# poas.net
KiCad netlist of a schematic drawn in EAGLE
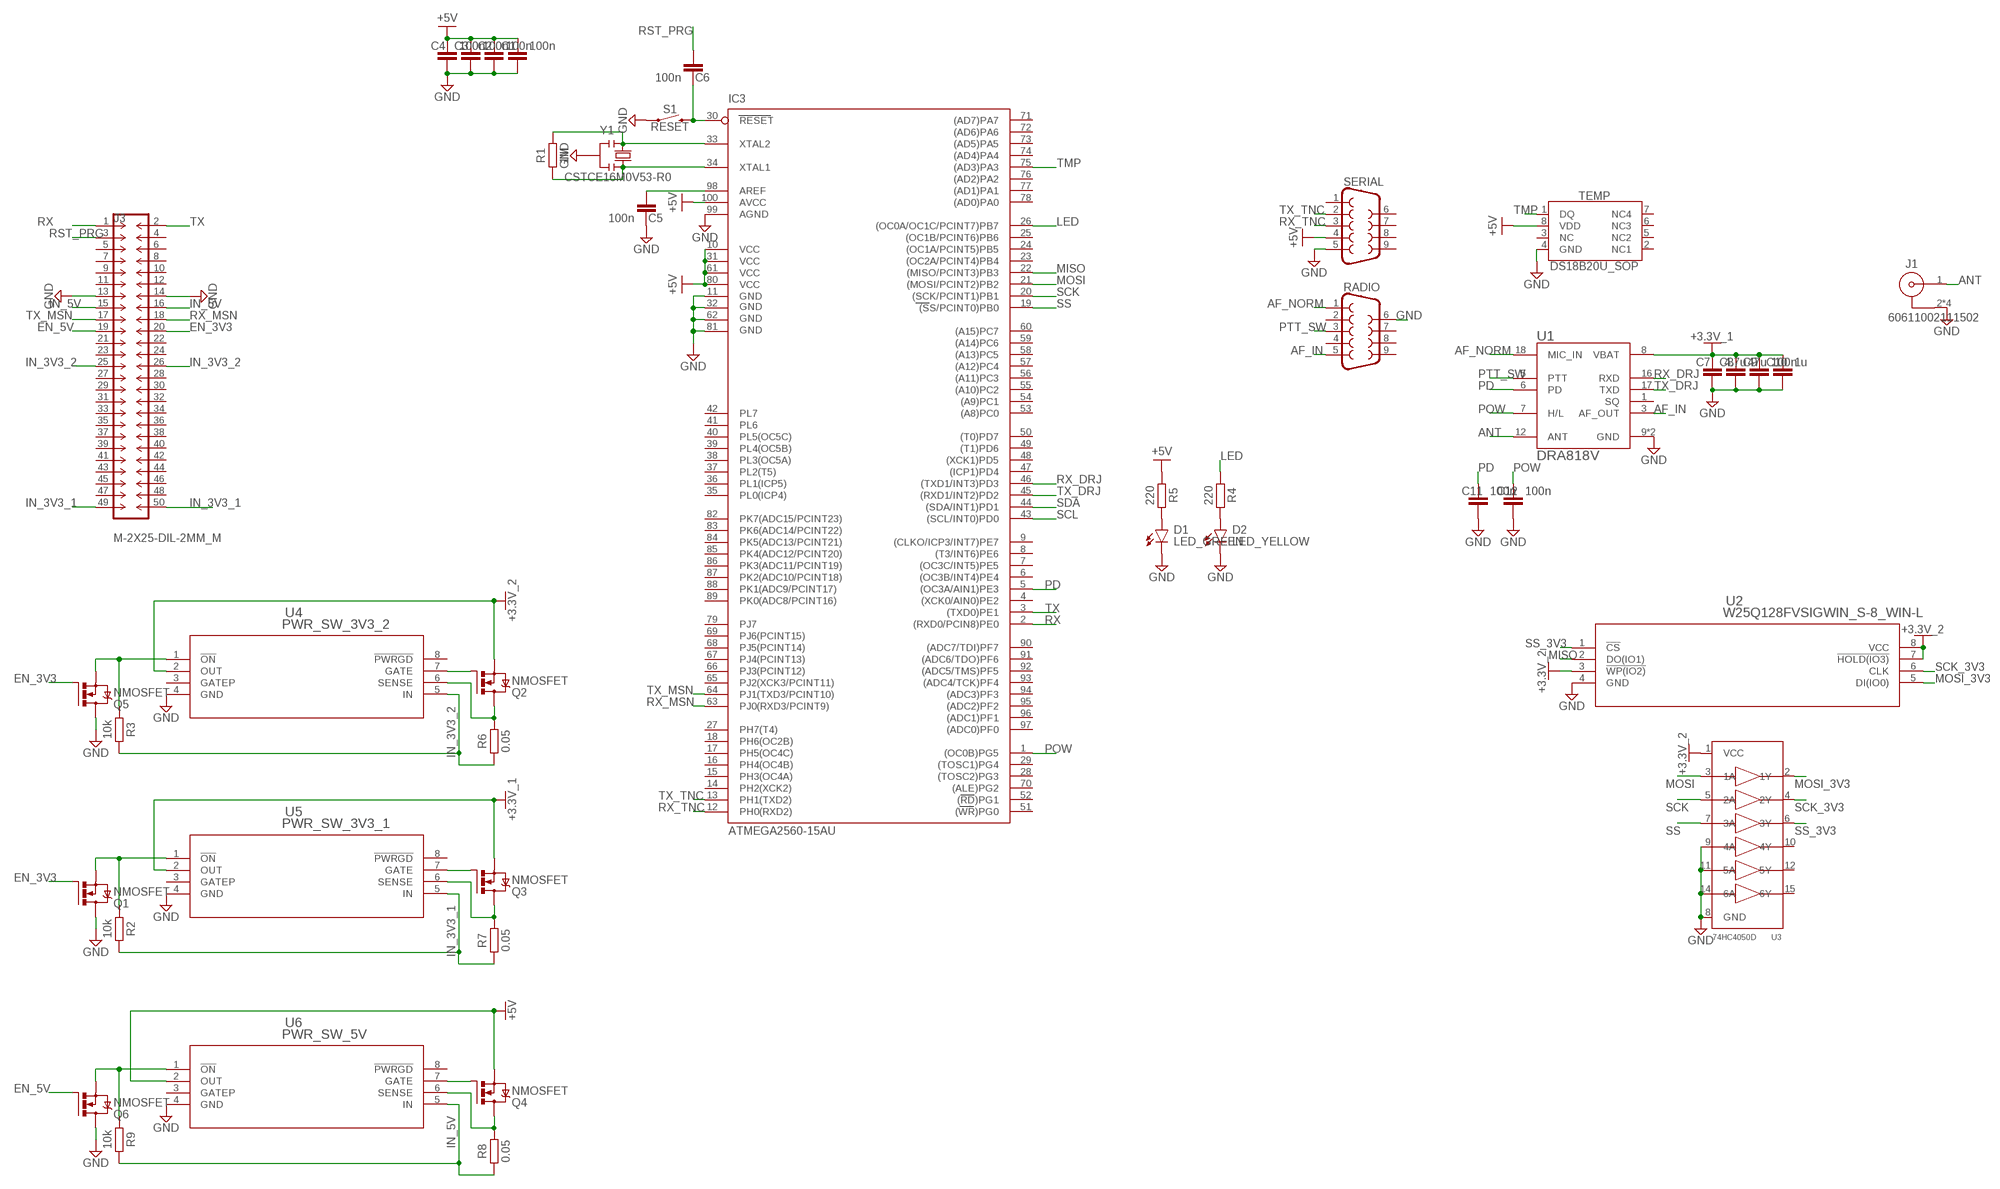
[diagram p0: schematic, sheet 1]

(export (version "E")
  (design (tool "Eeschema 10.0.6"))
  (components
    (comp (ref "C1")
      (value "100n")
      (footprint "eagle-import:CAPC1608X85")
      (libsource (lib "eagle-import") (part "CCHIP-0603(1608-METRIC)_"))
    )
    (comp (ref "C2")
      (value "100n")
      (footprint "eagle-import:CAPC1608X85")
      (libsource (lib "eagle-import") (part "CCHIP-0603(1608-METRIC)_"))
    )
    (comp (ref "C3")
      (value "100n")
      (footprint "eagle-import:CAPC1608X85")
      (libsource (lib "eagle-import") (part "CCHIP-0603(1608-METRIC)_"))
    )
    (comp (ref "C4")
      (value "100n")
      (footprint "eagle-import:CAPC1608X85")
      (libsource (lib "eagle-import") (part "CCHIP-0603(1608-METRIC)_"))
    )
    (comp (ref "C5")
      (value "100n")
      (footprint "eagle-import:CAPC1608X85")
      (libsource (lib "eagle-import") (part "CCHIP-0603(1608-METRIC)_"))
    )
    (comp (ref "C6")
      (value "100n")
      (footprint "eagle-import:CAPC1608X85")
      (libsource (lib "eagle-import") (part "CCHIP-0603(1608-METRIC)_"))
    )
    (comp (ref "C7")
      (value "4.7u")
      (footprint "eagle-import:CAPC1608X85")
      (libsource (lib "eagle-import") (part "CCHIP-0603(1608-METRIC)_"))
    )
    (comp (ref "C8")
      (value "47u")
      (footprint "eagle-import:CAPC1608X85")
      (libsource (lib "eagle-import") (part "CCHIP-0603(1608-METRIC)_"))
    )
    (comp (ref "C9")
      (value "100n")
      (footprint "eagle-import:CAPC1608X85")
      (libsource (lib "eagle-import") (part "CCHIP-0603(1608-METRIC)_"))
    )
    (comp (ref "C10")
      (value "1u")
      (footprint "eagle-import:CAPC1608X85")
      (libsource (lib "eagle-import") (part "CCHIP-0603(1608-METRIC)_"))
    )
    (comp (ref "C11")
      (value "100n")
      (footprint "eagle-import:CAPC1608X85")
      (libsource (lib "eagle-import") (part "CCHIP-0603(1608-METRIC)_"))
    )
    (comp (ref "C12")
      (value "100n")
      (footprint "eagle-import:CAPC1608X85")
      (libsource (lib "eagle-import") (part "CCHIP-0603(1608-METRIC)_"))
    )
    (comp (ref "D1")
      (value "LED_GREEN")
      (footprint "eagle-import:LEDC1608X55N_FLAT-G")
      (libsource (lib "eagle-import") (part "CHIP-FLAT-G_0603-0.55MM"))
    )
    (comp (ref "D2")
      (value "LED_YELLOW")
      (footprint "eagle-import:LEDC1608X55N_FLAT-Y")
      (libsource (lib "eagle-import") (part "CHIP-FLAT-Y_0603-0.55MM"))
    )
    (comp (ref "IC3")
      (value "ATMEGA2560-15AU")
      (footprint "eagle-import:TQFP100")
      (fields (field (name "PART_NUMBER") "ATMEGA2560-16AU"))
      (libsource (lib "eagle-import") (part "0023_ATMEGA2560-16AU"))
    )
    (comp (ref "J1")
      (value "60611002111502")
      (footprint "eagle-import:60611002111502")
      (libsource (lib "eagle-import") (part "60611002111502"))
    )
    (comp (ref "J3")
      (value "M-2X25-DIL-2MM_M")
      (footprint "eagle-import:DIL-2MM-2X25_M")
      (libsource (lib "eagle-import") (part "M-2X25-DIL-2MM_M"))
    )
    (comp (ref "Q1")
      (value "NMOSFET")
      (footprint "eagle-import:SOT23")
      (libsource (lib "eagle-import") (part "NMOSFETSOT23-GSD"))
    )
    (comp (ref "Q2")
      (value "NMOSFET")
      (footprint "eagle-import:SOT23")
      (libsource (lib "eagle-import") (part "NMOSFETSOT23-GSD"))
    )
    (comp (ref "Q3")
      (value "NMOSFET")
      (footprint "eagle-import:SOT23")
      (libsource (lib "eagle-import") (part "NMOSFETSOT23-GSD"))
    )
    (comp (ref "Q4")
      (value "NMOSFET")
      (footprint "eagle-import:SOT23")
      (libsource (lib "eagle-import") (part "NMOSFETSOT23-GSD"))
    )
    (comp (ref "Q5")
      (value "NMOSFET")
      (footprint "eagle-import:SOT23")
      (libsource (lib "eagle-import") (part "NMOSFETSOT23-GSD"))
    )
    (comp (ref "Q6")
      (value "NMOSFET")
      (footprint "eagle-import:SOT23")
      (libsource (lib "eagle-import") (part "NMOSFETSOT23-GSD"))
    )
    (comp (ref "R1")
      (value "1M")
      (footprint "eagle-import:RESC1608X60")
      (libsource (lib "eagle-import") (part "RCHIP-0603(1608-METRIC)_"))
    )
    (comp (ref "R2")
      (value "10k")
      (footprint "eagle-import:RESC1608X60")
      (libsource (lib "eagle-import") (part "RCHIP-0603(1608-METRIC)_"))
    )
    (comp (ref "R3")
      (value "10k")
      (footprint "eagle-import:RESC1608X60")
      (libsource (lib "eagle-import") (part "RCHIP-0603(1608-METRIC)_"))
    )
    (comp (ref "R4")
      (value "220")
      (footprint "eagle-import:RESC1608X60")
      (libsource (lib "eagle-import") (part "RCHIP-0603(1608-METRIC)_"))
    )
    (comp (ref "R5")
      (value "220")
      (footprint "eagle-import:RESC1608X60")
      (libsource (lib "eagle-import") (part "RCHIP-0603(1608-METRIC)_"))
    )
    (comp (ref "R6")
      (value "0.05")
      (footprint "eagle-import:RESC1608X60")
      (libsource (lib "eagle-import") (part "RCHIP-0603(1608-METRIC)_"))
    )
    (comp (ref "R7")
      (value "0.05")
      (footprint "eagle-import:RESC1608X60")
      (libsource (lib "eagle-import") (part "RCHIP-0603(1608-METRIC)_"))
    )
    (comp (ref "R8")
      (value "0.05")
      (footprint "eagle-import:RESC1608X60")
      (libsource (lib "eagle-import") (part "RCHIP-0603(1608-METRIC)_"))
    )
    (comp (ref "R9")
      (value "10k")
      (footprint "eagle-import:RESC1608X60")
      (libsource (lib "eagle-import") (part "RCHIP-0603(1608-METRIC)_"))
    )
    (comp (ref "RADIO")
      (value "DB9MALE")
      (footprint "eagle-import:DB9_MALE")
      (libsource (lib "eagle-import") (part "DB9MALE"))
    )
    (comp (ref "S1")
      (value "RESET")
      (footprint "eagle-import:TACTILE_SWITCH_SMD_6.2MM_TALL")
      (libsource (lib "eagle-import") (part "MOMENTARY-SWITCH-SPST-SMD-6.2MM-TALL"))
    )
    (comp (ref "SERIAL")
      (value "DB9MALE")
      (footprint "eagle-import:DB9_MALE")
      (libsource (lib "eagle-import") (part "DB9MALE"))
    )
    (comp (ref "TEMP")
      (value "DS18B20U_SOP")
      (footprint "eagle-import:SOP65P491X110-8N")
      (libsource (lib "eagle-import") (part "DS18B20U_SOP"))
    )
    (comp (ref "U1")
      (value "DRA818V")
      (footprint "eagle-import:DORJI_DRA818V")
      (fields (field (name "MANUFACTURER") "DORJI"))
      (libsource (lib "eagle-import") (part "DRA818V"))
    )
    (comp (ref "U2")
      (value "W25Q128FVSIGWIN_S-8_WIN-L")
      (footprint "eagle-import:WIN_S-8_WIN-L")
      (fields
        (field (name "MANUFACTURER_PART_NUMBER") "W25Q128FVSIG")
        (field (name "COPYRIGHT") "Copyright (C) 2023 Ultra Librarian. All rights reserved.")
      )
      (libsource (lib "eagle-import") (part "W25Q128FVSIGWIN_S-8_WIN-L"))
    )
    (comp (ref "U3")
      (value "74HC4050D")
      (footprint "eagle-import:TSSOP16")
      (libsource (lib "eagle-import") (part "74HC4050DTSSOP"))
    )
    (comp (ref "U4")
      (value "PWR_SW_3V3_2")
      (footprint "eagle-import:TSOT-23_TS8_LIT-L")
      (fields
        (field (name "MANUFACTURER_PART_NUMBER") "LTC4361CTS8-2#TRMPBF")
        (field (name "COPYRIGHT") "Copyright (C) 2023 Ultra Librarian. All rights reserved.")
      )
      (libsource (lib "eagle-import") (part "LTC4361CTS8-2TRMPBFTSOT-23_TS8_LIT-L"))
    )
    (comp (ref "U5")
      (value "PWR_SW_3V3_1")
      (footprint "eagle-import:TSOT-23_TS8_LIT-L")
      (fields
        (field (name "MANUFACTURER_PART_NUMBER") "LTC4361CTS8-2#TRMPBF")
        (field (name "COPYRIGHT") "Copyright (C) 2023 Ultra Librarian. All rights reserved.")
      )
      (libsource (lib "eagle-import") (part "LTC4361CTS8-2TRMPBFTSOT-23_TS8_LIT-L"))
    )
    (comp (ref "U6")
      (value "PWR_SW_5V")
      (footprint "eagle-import:TSOT-23_TS8_LIT-L")
      (fields
        (field (name "MANUFACTURER_PART_NUMBER") "LTC4361CTS8-2#TRMPBF")
        (field (name "COPYRIGHT") "Copyright (C) 2023 Ultra Librarian. All rights reserved.")
      )
      (libsource (lib "eagle-import") (part "LTC4361CTS8-2TRMPBFTSOT-23_TS8_LIT-L"))
    )
    (comp (ref "Y1")
      (value "CSTCE16M0V53-R0")
      (footprint "eagle-import:RESONATOR")
      (libsource (lib "eagle-import") (part "0011_CSTCE16M0V53-R0"))
    )
  )
  (nets
    (net (code "1") (name "+3.3V_1") (class "Default")
      (node (ref "C10") (pin "1") (pinfunction "1_1") (pintype "passive"))
      (node (ref "C7") (pin "1") (pinfunction "1_1") (pintype "passive"))
      (node (ref "C8") (pin "1") (pinfunction "1_1") (pintype "passive"))
      (node (ref "C9") (pin "1") (pinfunction "1_1") (pintype "passive"))
      (node (ref "Q3") (pin "2") (pinfunction "S_2") (pintype "passive"))
      (node (ref "U1") (pin "8") (pinfunction "VBAT_8") (pintype "power_in"))
      (node (ref "U5") (pin "2") (pinfunction "OUT_2") (pintype "output"))
    )
    (net (code "2") (name "+3.3V_2") (class "Default")
      (node (ref "Q2") (pin "2") (pinfunction "S_2") (pintype "passive"))
      (node (ref "U2") (pin "3") (pinfunction "~{WP(IO2})_3") (pintype "bidirectional"))
      (node (ref "U2") (pin "7") (pinfunction "~{HOLD(IO3})_7") (pintype "bidirectional"))
      (node (ref "U2") (pin "8") (pinfunction "VCC_8") (pintype "power_in"))
      (node (ref "U3") (pin "1") (pinfunction "VCC_1") (pintype "bidirectional"))
      (node (ref "U4") (pin "2") (pinfunction "OUT_2") (pintype "output"))
    )
    (net (code "3") (name "+5V") (class "Default")
      (node (ref "C1") (pin "1") (pinfunction "1_1") (pintype "passive"))
      (node (ref "C2") (pin "1") (pinfunction "1_1") (pintype "passive"))
      (node (ref "C3") (pin "1") (pinfunction "1_1") (pintype "passive"))
      (node (ref "C4") (pin "1") (pinfunction "1_1") (pintype "passive"))
      (node (ref "IC3") (pin "10") (pinfunction "VCC_10") (pintype "power_in"))
      (node (ref "IC3") (pin "100") (pinfunction "AVCC_100") (pintype "power_in"))
      (node (ref "IC3") (pin "31") (pinfunction "VCC1_31") (pintype "power_in"))
      (node (ref "IC3") (pin "61") (pinfunction "VCC2_61") (pintype "power_in"))
      (node (ref "IC3") (pin "80") (pinfunction "VCC3_80") (pintype "power_in"))
      (node (ref "Q4") (pin "2") (pinfunction "S_2") (pintype "passive"))
      (node (ref "R5") (pin "1") (pinfunction "1_1") (pintype "passive"))
      (node (ref "SERIAL") (pin "4") (pinfunction "4_4") (pintype "passive"))
      (node (ref "TEMP") (pin "8") (pinfunction "VDD_8") (pintype "bidirectional"))
      (node (ref "U6") (pin "2") (pinfunction "OUT_2") (pintype "output"))
    )
    (net (code "4") (name "/AF_IN") (class "Default")
      (node (ref "RADIO") (pin "5") (pinfunction "5_5") (pintype "passive"))
      (node (ref "U1") (pin "3") (pinfunction "AF_OUT_3") (pintype "output"))
    )
    (net (code "5") (name "/AF_NORM") (class "Default")
      (node (ref "RADIO") (pin "1") (pinfunction "1_1") (pintype "passive"))
      (node (ref "U1") (pin "18") (pinfunction "MIC_IN_18") (pintype "input"))
    )
    (net (code "6") (name "/ANT") (class "Default")
      (node (ref "J1") (pin "1") (pinfunction "1_1") (pintype "passive"))
      (node (ref "U1") (pin "12") (pinfunction "ANT_12") (pintype "passive"))
    )
    (net (code "7") (name "/EN_3V3") (class "Default")
      (node (ref "J3") (pin "20") (pinfunction "20_20") (pintype "passive"))
      (node (ref "Q1") (pin "1") (pinfunction "G_1") (pintype "passive"))
      (node (ref "Q5") (pin "1") (pinfunction "G_1") (pintype "passive"))
    )
    (net (code "8") (name "/EN_5V") (class "Default")
      (node (ref "J3") (pin "19") (pinfunction "19_19") (pintype "passive"))
      (node (ref "Q6") (pin "1") (pinfunction "G_1") (pintype "passive"))
    )
    (net (code "9") (name "/IN_3V3_1") (class "Default")
      (node (ref "J3") (pin "49") (pinfunction "49_49") (pintype "passive"))
      (node (ref "J3") (pin "50") (pinfunction "50_50") (pintype "passive"))
      (node (ref "R2") (pin "2") (pinfunction "2_2") (pintype "passive"))
      (node (ref "R7") (pin "1") (pinfunction "1_1") (pintype "passive"))
      (node (ref "U5") (pin "5") (pinfunction "IN_5") (pintype "input"))
    )
    (net (code "10") (name "/IN_3V3_2") (class "Default")
      (node (ref "J3") (pin "25") (pinfunction "25_25") (pintype "passive"))
      (node (ref "J3") (pin "26") (pinfunction "26_26") (pintype "passive"))
      (node (ref "R3") (pin "2") (pinfunction "2_2") (pintype "passive"))
      (node (ref "R6") (pin "1") (pinfunction "1_1") (pintype "passive"))
      (node (ref "U4") (pin "5") (pinfunction "IN_5") (pintype "input"))
    )
    (net (code "11") (name "/IN_5V") (class "Default")
      (node (ref "J3") (pin "15") (pinfunction "15_15") (pintype "passive"))
      (node (ref "J3") (pin "16") (pinfunction "16_16") (pintype "passive"))
      (node (ref "R8") (pin "1") (pinfunction "1_1") (pintype "passive"))
      (node (ref "R9") (pin "2") (pinfunction "2_2") (pintype "passive"))
      (node (ref "U6") (pin "5") (pinfunction "IN_5") (pintype "input"))
    )
    (net (code "12") (name "/LED") (class "Default")
      (node (ref "IC3") (pin "26") (pinfunction "(OC0A/OC1C/PCINT7)PB7_26") (pintype "bidirectional"))
      (node (ref "R4") (pin "1") (pinfunction "1_1") (pintype "passive"))
    )
    (net (code "13") (name "/MISO") (class "Default")
      (node (ref "IC3") (pin "22") (pinfunction "(MISO/PCINT3)PB3_22") (pintype "bidirectional"))
      (node (ref "U2") (pin "2") (pinfunction "DO(IO1)_2") (pintype "bidirectional"))
    )
    (net (code "14") (name "/MOSI") (class "Default")
      (node (ref "IC3") (pin "21") (pinfunction "(MOSI/PCINT2)PB2_21") (pintype "bidirectional"))
      (node (ref "U3") (pin "3") (pinfunction "1A_3") (pintype "bidirectional"))
    )
    (net (code "15") (name "/MOSI_3V3") (class "Default")
      (node (ref "U2") (pin "5") (pinfunction "DI(IO0)_5") (pintype "bidirectional"))
      (node (ref "U3") (pin "2") (pinfunction "1Y_2") (pintype "bidirectional"))
    )
    (net (code "16") (name "/PD") (class "Default")
      (node (ref "C11") (pin "1") (pinfunction "1_1") (pintype "passive"))
      (node (ref "IC3") (pin "5") (pinfunction "(OC3A/AIN1)PE3_5") (pintype "bidirectional"))
      (node (ref "U1") (pin "6") (pinfunction "PD_6") (pintype "input"))
    )
    (net (code "17") (name "/POW") (class "Default")
      (node (ref "C12") (pin "1") (pinfunction "1_1") (pintype "passive"))
      (node (ref "IC3") (pin "1") (pinfunction "(OC0B)PG5_1") (pintype "bidirectional"))
      (node (ref "U1") (pin "7") (pinfunction "H/L_7") (pintype "input"))
    )
    (net (code "18") (name "/PTT_SW") (class "Default")
      (node (ref "RADIO") (pin "3") (pinfunction "3_3") (pintype "passive"))
      (node (ref "U1") (pin "5") (pinfunction "PTT_5") (pintype "input"))
    )
    (net (code "19") (name "/RST_PRG") (class "Default")
      (node (ref "C6") (pin "2") (pinfunction "2_2") (pintype "passive"))
      (node (ref "J3") (pin "3") (pinfunction "3_3") (pintype "passive"))
    )
    (net (code "20") (name "/RX") (class "Default")
      (node (ref "IC3") (pin "2") (pinfunction "(RXD0/PCIN8)PE0_2") (pintype "bidirectional"))
      (node (ref "J3") (pin "1") (pinfunction "1_1") (pintype "passive"))
    )
    (net (code "21") (name "/RX_DRJ") (class "Default")
      (node (ref "IC3") (pin "46") (pinfunction "(TXD1/INT3)PD3_46") (pintype "bidirectional"))
      (node (ref "U1") (pin "16") (pinfunction "RXD_16") (pintype "input"))
    )
    (net (code "22") (name "/RX_MSN") (class "Default")
      (node (ref "IC3") (pin "63") (pinfunction "PJ0(RXD3/PCINT9)_63") (pintype "bidirectional"))
      (node (ref "J3") (pin "18") (pinfunction "18_18") (pintype "passive"))
    )
    (net (code "23") (name "/RX_TNC") (class "Default")
      (node (ref "IC3") (pin "12") (pinfunction "PH0(RXD2)_12") (pintype "bidirectional"))
      (node (ref "SERIAL") (pin "3") (pinfunction "3_3") (pintype "passive"))
    )
    (net (code "24") (name "/SCK") (class "Default")
      (node (ref "IC3") (pin "20") (pinfunction "(SCK/PCINT1)PB1_20") (pintype "bidirectional"))
      (node (ref "U3") (pin "5") (pinfunction "2A_5") (pintype "bidirectional"))
    )
    (net (code "25") (name "/SCK_3V3") (class "Default")
      (node (ref "U2") (pin "6") (pinfunction "CLK_6") (pintype "input"))
      (node (ref "U3") (pin "4") (pinfunction "2Y_4") (pintype "bidirectional"))
    )
    (net (code "26") (name "/SCL") (class "Default")
      (node (ref "IC3") (pin "43") (pinfunction "(SCL/INT0)PD0_43") (pintype "bidirectional"))
    )
    (net (code "27") (name "/SDA") (class "Default")
      (node (ref "IC3") (pin "44") (pinfunction "(SDA/INT1)PD1_44") (pintype "bidirectional"))
    )
    (net (code "28") (name "/SS") (class "Default")
      (node (ref "IC3") (pin "19") (pinfunction "(SS/PCINT0)PB0_19") (pintype "bidirectional"))
      (node (ref "U3") (pin "7") (pinfunction "3A_7") (pintype "bidirectional"))
    )
    (net (code "29") (name "/SS_3V3") (class "Default")
      (node (ref "U2") (pin "1") (pinfunction "~{CS}_1") (pintype "input"))
      (node (ref "U3") (pin "6") (pinfunction "3Y_6") (pintype "bidirectional"))
    )
    (net (code "30") (name "/TMP") (class "Default")
      (node (ref "IC3") (pin "75") (pinfunction "(AD3)PA3_75") (pintype "bidirectional"))
      (node (ref "TEMP") (pin "1") (pinfunction "DQ_1") (pintype "bidirectional"))
    )
    (net (code "31") (name "/TX") (class "Default")
      (node (ref "IC3") (pin "3") (pinfunction "(TXD0)PE1_3") (pintype "bidirectional"))
      (node (ref "J3") (pin "2") (pinfunction "2_2") (pintype "passive"))
    )
    (net (code "32") (name "/TX_DRJ") (class "Default")
      (node (ref "IC3") (pin "45") (pinfunction "(RXD1/INT2)PD2_45") (pintype "bidirectional"))
      (node (ref "U1") (pin "17") (pinfunction "TXD_17") (pintype "output"))
    )
    (net (code "33") (name "/TX_MSN") (class "Default")
      (node (ref "IC3") (pin "64") (pinfunction "PJ1(TXD3/PCINT10)_64") (pintype "bidirectional"))
      (node (ref "J3") (pin "17") (pinfunction "17_17") (pintype "passive"))
    )
    (net (code "34") (name "/TX_TNC") (class "Default")
      (node (ref "IC3") (pin "13") (pinfunction "PH1(TXD2)_13") (pintype "bidirectional"))
      (node (ref "SERIAL") (pin "2") (pinfunction "2_2") (pintype "passive"))
    )
    (net (code "35") (name "GND") (class "Default")
      (node (ref "C1") (pin "2") (pinfunction "2_2") (pintype "passive"))
      (node (ref "C10") (pin "2") (pinfunction "2_2") (pintype "passive"))
      (node (ref "C11") (pin "2") (pinfunction "2_2") (pintype "passive"))
      (node (ref "C12") (pin "2") (pinfunction "2_2") (pintype "passive"))
      (node (ref "C2") (pin "2") (pinfunction "2_2") (pintype "passive"))
      (node (ref "C3") (pin "2") (pinfunction "2_2") (pintype "passive"))
      (node (ref "C4") (pin "2") (pinfunction "2_2") (pintype "passive"))
      (node (ref "C5") (pin "1") (pinfunction "1_1") (pintype "passive"))
      (node (ref "C7") (pin "2") (pinfunction "2_2") (pintype "passive"))
      (node (ref "C8") (pin "2") (pinfunction "2_2") (pintype "passive"))
      (node (ref "C9") (pin "2") (pinfunction "2_2") (pintype "passive"))
      (node (ref "D1") (pin "C") (pinfunction "C_C") (pintype "passive"))
      (node (ref "D2") (pin "C") (pinfunction "C_C") (pintype "passive"))
      (node (ref "IC3") (pin "11") (pinfunction "GND_11") (pintype "power_in"))
      (node (ref "IC3") (pin "32") (pinfunction "GND1_32") (pintype "power_in"))
      (node (ref "IC3") (pin "62") (pinfunction "GND2_62") (pintype "power_in"))
      (node (ref "IC3") (pin "81") (pinfunction "GND3_81") (pintype "power_in"))
      (node (ref "IC3") (pin "99") (pinfunction "AGND_99") (pintype "power_in"))
      (node (ref "J1") (pin "2") (pinfunction "2_2") (pintype "passive"))
      (node (ref "J1") (pin "3") (pinfunction "2_3") (pintype "passive"))
      (node (ref "J1") (pin "4") (pinfunction "2_4") (pintype "passive"))
      (node (ref "J1") (pin "5") (pinfunction "2_5") (pintype "passive"))
      (node (ref "J3") (pin "13") (pinfunction "13_13") (pintype "passive"))
      (node (ref "J3") (pin "14") (pinfunction "14_14") (pintype "passive"))
      (node (ref "Q1") (pin "3") (pinfunction "D_3") (pintype "passive"))
      (node (ref "Q5") (pin "3") (pinfunction "D_3") (pintype "passive"))
      (node (ref "Q6") (pin "3") (pinfunction "D_3") (pintype "passive"))
      (node (ref "RADIO") (pin "6") (pinfunction "6_6") (pintype "passive"))
      (node (ref "S1") (pin "A2") (pinfunction "1_A2") (pintype "passive"))
      (node (ref "SERIAL") (pin "5") (pinfunction "5_5") (pintype "passive"))
      (node (ref "TEMP") (pin "4") (pinfunction "GND_4") (pintype "bidirectional"))
      (node (ref "U1") (pin "10") (pinfunction "GND_10") (pintype "power_in"))
      (node (ref "U1") (pin "9") (pinfunction "GND_9") (pintype "power_in"))
      (node (ref "U2") (pin "4") (pinfunction "GND_4") (pintype "power_in"))
      (node (ref "U3") (pin "11") (pinfunction "5A_11") (pintype "bidirectional"))
      (node (ref "U3") (pin "14") (pinfunction "6A_14") (pintype "bidirectional"))
      (node (ref "U3") (pin "8") (pinfunction "GND_8") (pintype "bidirectional"))
      (node (ref "U3") (pin "9") (pinfunction "4A_9") (pintype "bidirectional"))
      (node (ref "U4") (pin "4") (pinfunction "GND_4") (pintype "power_in"))
      (node (ref "U5") (pin "4") (pinfunction "GND_4") (pintype "power_in"))
      (node (ref "U6") (pin "4") (pinfunction "GND_4") (pintype "power_in"))
      (node (ref "Y1") (pin "2") (pinfunction "2_2") (pintype "passive"))
    )
    (net (code "36") (name "Net-(D1-PadA)") (class "Default")
      (node (ref "D1") (pin "A") (pinfunction "A_A") (pintype "passive"))
      (node (ref "R5") (pin "2") (pinfunction "2_2") (pintype "passive"))
    )
    (net (code "37") (name "Net-(D2-PadA)") (class "Default")
      (node (ref "D2") (pin "A") (pinfunction "A_A") (pintype "passive"))
      (node (ref "R4") (pin "2") (pinfunction "2_2") (pintype "passive"))
    )
    (net (code "38") (name "Net-(IC3-AREF)") (class "Default")
      (node (ref "C5") (pin "2") (pinfunction "2_2") (pintype "passive"))
      (node (ref "IC3") (pin "98") (pinfunction "AREF_98") (pintype "bidirectional"))
    )
    (net (code "39") (name "Net-(IC3-RESET)") (class "Default")
      (node (ref "C6") (pin "1") (pinfunction "1_1") (pintype "passive"))
      (node (ref "IC3") (pin "30") (pinfunction "RESET_30") (pintype "input"))
      (node (ref "S1") (pin "B2") (pinfunction "2_B2") (pintype "passive"))
    )
    (net (code "40") (name "Net-(IC3-XTAL1)") (class "Default")
      (node (ref "IC3") (pin "34") (pinfunction "XTAL1_34") (pintype "input"))
      (node (ref "R1") (pin "1") (pinfunction "1_1") (pintype "passive"))
      (node (ref "Y1") (pin "3") (pinfunction "3_3") (pintype "passive"))
    )
    (net (code "41") (name "Net-(IC3-XTAL2)") (class "Default")
      (node (ref "IC3") (pin "33") (pinfunction "XTAL2_33") (pintype "output"))
      (node (ref "R1") (pin "2") (pinfunction "2_2") (pintype "passive"))
      (node (ref "Y1") (pin "1") (pinfunction "1_1") (pintype "passive"))
    )
    (net (code "42") (name "Net-(Q1-S)") (class "Default")
      (node (ref "Q1") (pin "2") (pinfunction "S_2") (pintype "passive"))
      (node (ref "R2") (pin "1") (pinfunction "1_1") (pintype "passive"))
      (node (ref "U5") (pin "1") (pinfunction "~{ON}_1") (pintype "input"))
    )
    (net (code "43") (name "Net-(Q2-D)") (class "Default")
      (node (ref "Q2") (pin "3") (pinfunction "D_3") (pintype "passive"))
      (node (ref "R6") (pin "2") (pinfunction "2_2") (pintype "passive"))
      (node (ref "U4") (pin "6") (pinfunction "SENSE_6") (pintype "input"))
    )
    (net (code "44") (name "Net-(Q2-G)") (class "Default")
      (node (ref "Q2") (pin "1") (pinfunction "G_1") (pintype "passive"))
      (node (ref "U4") (pin "7") (pinfunction "GATE_7") (pintype "passive"))
    )
    (net (code "45") (name "Net-(Q3-D)") (class "Default")
      (node (ref "Q3") (pin "3") (pinfunction "D_3") (pintype "passive"))
      (node (ref "R7") (pin "2") (pinfunction "2_2") (pintype "passive"))
      (node (ref "U5") (pin "6") (pinfunction "SENSE_6") (pintype "input"))
    )
    (net (code "46") (name "Net-(Q3-G)") (class "Default")
      (node (ref "Q3") (pin "1") (pinfunction "G_1") (pintype "passive"))
      (node (ref "U5") (pin "7") (pinfunction "GATE_7") (pintype "passive"))
    )
    (net (code "47") (name "Net-(Q4-D)") (class "Default")
      (node (ref "Q4") (pin "3") (pinfunction "D_3") (pintype "passive"))
      (node (ref "R8") (pin "2") (pinfunction "2_2") (pintype "passive"))
      (node (ref "U6") (pin "6") (pinfunction "SENSE_6") (pintype "input"))
    )
    (net (code "48") (name "Net-(Q4-G)") (class "Default")
      (node (ref "Q4") (pin "1") (pinfunction "G_1") (pintype "passive"))
      (node (ref "U6") (pin "7") (pinfunction "GATE_7") (pintype "passive"))
    )
    (net (code "49") (name "Net-(Q5-S)") (class "Default")
      (node (ref "Q5") (pin "2") (pinfunction "S_2") (pintype "passive"))
      (node (ref "R3") (pin "1") (pinfunction "1_1") (pintype "passive"))
      (node (ref "U4") (pin "1") (pinfunction "~{ON}_1") (pintype "input"))
    )
    (net (code "50") (name "Net-(Q6-S)") (class "Default")
      (node (ref "Q6") (pin "2") (pinfunction "S_2") (pintype "passive"))
      (node (ref "R9") (pin "1") (pinfunction "1_1") (pintype "passive"))
      (node (ref "U6") (pin "1") (pinfunction "~{ON}_1") (pintype "input"))
    )
    (net (code "51") (name "unconnected-(IC3-(A8)PC0-Pad53)") (class "Default")
      (node (ref "IC3") (pin "53") (pinfunction "(A8)PC0_53") (pintype "bidirectional"))
    )
    (net (code "52") (name "unconnected-(IC3-(A9)PC1-Pad54)") (class "Default")
      (node (ref "IC3") (pin "54") (pinfunction "(A9)PC1_54") (pintype "bidirectional"))
    )
    (net (code "53") (name "unconnected-(IC3-(A10)PC2-Pad55)") (class "Default")
      (node (ref "IC3") (pin "55") (pinfunction "(A10)PC2_55") (pintype "bidirectional"))
    )
    (net (code "54") (name "unconnected-(IC3-(A11)PC3-Pad56)") (class "Default")
      (node (ref "IC3") (pin "56") (pinfunction "(A11)PC3_56") (pintype "bidirectional"))
    )
    (net (code "55") (name "unconnected-(IC3-(A12)PC4-Pad57)") (class "Default")
      (node (ref "IC3") (pin "57") (pinfunction "(A12)PC4_57") (pintype "bidirectional"))
    )
    (net (code "56") (name "unconnected-(IC3-(A13)PC5-Pad58)") (class "Default")
      (node (ref "IC3") (pin "58") (pinfunction "(A13)PC5_58") (pintype "bidirectional"))
    )
    (net (code "57") (name "unconnected-(IC3-(A14)PC6-Pad59)") (class "Default")
      (node (ref "IC3") (pin "59") (pinfunction "(A14)PC6_59") (pintype "bidirectional"))
    )
    (net (code "58") (name "unconnected-(IC3-(A15)PC7-Pad60)") (class "Default")
      (node (ref "IC3") (pin "60") (pinfunction "(A15)PC7_60") (pintype "bidirectional"))
    )
    (net (code "59") (name "unconnected-(IC3-(AD0)PA0-Pad78)") (class "Default")
      (node (ref "IC3") (pin "78") (pinfunction "(AD0)PA0_78") (pintype "bidirectional"))
    )
    (net (code "60") (name "unconnected-(IC3-(AD1)PA1-Pad77)") (class "Default")
      (node (ref "IC3") (pin "77") (pinfunction "(AD1)PA1_77") (pintype "bidirectional"))
    )
    (net (code "61") (name "unconnected-(IC3-(AD2)PA2-Pad76)") (class "Default")
      (node (ref "IC3") (pin "76") (pinfunction "(AD2)PA2_76") (pintype "bidirectional"))
    )
    (net (code "62") (name "unconnected-(IC3-(AD4)PA4-Pad74)") (class "Default")
      (node (ref "IC3") (pin "74") (pinfunction "(AD4)PA4_74") (pintype "bidirectional"))
    )
    (net (code "63") (name "unconnected-(IC3-(AD5)PA5-Pad73)") (class "Default")
      (node (ref "IC3") (pin "73") (pinfunction "(AD5)PA5_73") (pintype "bidirectional"))
    )
    (net (code "64") (name "unconnected-(IC3-(AD6)PA6-Pad72)") (class "Default")
      (node (ref "IC3") (pin "72") (pinfunction "(AD6)PA6_72") (pintype "bidirectional"))
    )
    (net (code "65") (name "unconnected-(IC3-(AD7)PA7-Pad71)") (class "Default")
      (node (ref "IC3") (pin "71") (pinfunction "(AD7)PA7_71") (pintype "bidirectional"))
    )
    (net (code "66") (name "unconnected-(IC3-(ADC0)PF0-Pad97)") (class "Default")
      (node (ref "IC3") (pin "97") (pinfunction "(ADC0)PF0_97") (pintype "bidirectional"))
    )
    (net (code "67") (name "unconnected-(IC3-(ADC1)PF1-Pad96)") (class "Default")
      (node (ref "IC3") (pin "96") (pinfunction "(ADC1)PF1_96") (pintype "bidirectional"))
    )
    (net (code "68") (name "unconnected-(IC3-(ADC2)PF2-Pad95)") (class "Default")
      (node (ref "IC3") (pin "95") (pinfunction "(ADC2)PF2_95") (pintype "bidirectional"))
    )
    (net (code "69") (name "unconnected-(IC3-(ADC3)PF3-Pad94)") (class "Default")
      (node (ref "IC3") (pin "94") (pinfunction "(ADC3)PF3_94") (pintype "bidirectional"))
    )
    (net (code "70") (name "unconnected-(IC3-(ADC4{slash}TCK)PF4-Pad93)") (class "Default")
      (node (ref "IC3") (pin "93") (pinfunction "(ADC4/TCK)PF4_93") (pintype "bidirectional"))
    )
    (net (code "71") (name "unconnected-(IC3-(ADC5{slash}TMS)PF5-Pad92)") (class "Default")
      (node (ref "IC3") (pin "92") (pinfunction "(ADC5/TMS)PF5_92") (pintype "bidirectional"))
    )
    (net (code "72") (name "unconnected-(IC3-(ADC6{slash}TDO)PF6-Pad91)") (class "Default")
      (node (ref "IC3") (pin "91") (pinfunction "(ADC6/TDO)PF6_91") (pintype "bidirectional"))
    )
    (net (code "73") (name "unconnected-(IC3-(ADC7{slash}TDI)PF7-Pad90)") (class "Default")
      (node (ref "IC3") (pin "90") (pinfunction "(ADC7/TDI)PF7_90") (pintype "bidirectional"))
    )
    (net (code "74") (name "unconnected-(IC3-(ALE)PG2-Pad70)") (class "Default")
      (node (ref "IC3") (pin "70") (pinfunction "(ALE)PG2_70") (pintype "bidirectional"))
    )
    (net (code "75") (name "unconnected-(IC3-(CLKO{slash}ICP3{slash}INT7)PE7-Pad9)") (class "Default")
      (node (ref "IC3") (pin "9") (pinfunction "(CLKO/ICP3/INT7)PE7_9") (pintype "bidirectional"))
    )
    (net (code "76") (name "unconnected-(IC3-(ICP1)PD4-Pad47)") (class "Default")
      (node (ref "IC3") (pin "47") (pinfunction "(ICP1)PD4_47") (pintype "bidirectional"))
    )
    (net (code "77") (name "unconnected-(IC3-(OC1A{slash}PCINT5)PB5-Pad24)") (class "Default")
      (node (ref "IC3") (pin "24") (pinfunction "(OC1A/PCINT5)PB5_24") (pintype "bidirectional"))
    )
    (net (code "78") (name "unconnected-(IC3-(OC1B{slash}PCINT6)PB6-Pad25)") (class "Default")
      (node (ref "IC3") (pin "25") (pinfunction "(OC1B/PCINT6)PB6_25") (pintype "bidirectional"))
    )
    (net (code "79") (name "unconnected-(IC3-(OC2A{slash}PCINT4)PB4-Pad23)") (class "Default")
      (node (ref "IC3") (pin "23") (pinfunction "(OC2A/PCINT4)PB4_23") (pintype "bidirectional"))
    )
    (net (code "80") (name "unconnected-(IC3-(OC3B{slash}INT4)PE4-Pad6)") (class "Default")
      (node (ref "IC3") (pin "6") (pinfunction "(OC3B/INT4)PE4_6") (pintype "bidirectional"))
    )
    (net (code "81") (name "unconnected-(IC3-(OC3C{slash}INT5)PE5-Pad7)") (class "Default")
      (node (ref "IC3") (pin "7") (pinfunction "(OC3C/INT5)PE5_7") (pintype "bidirectional"))
    )
    (net (code "82") (name "unconnected-(IC3-(RD)PG1-Pad52)") (class "Default")
      (node (ref "IC3") (pin "52") (pinfunction "(RD)PG1_52") (pintype "bidirectional"))
    )
    (net (code "83") (name "unconnected-(IC3-(T0)PD7-Pad50)") (class "Default")
      (node (ref "IC3") (pin "50") (pinfunction "(T0)PD7_50") (pintype "bidirectional"))
    )
    (net (code "84") (name "unconnected-(IC3-(T1)PD6-Pad49)") (class "Default")
      (node (ref "IC3") (pin "49") (pinfunction "(T1)PD6_49") (pintype "bidirectional"))
    )
    (net (code "85") (name "unconnected-(IC3-(T3{slash}INT6)PE6-Pad8)") (class "Default")
      (node (ref "IC3") (pin "8") (pinfunction "(T3/INT6)PE6_8") (pintype "bidirectional"))
    )
    (net (code "86") (name "unconnected-(IC3-(TOSC1)PG4-Pad29)") (class "Default")
      (node (ref "IC3") (pin "29") (pinfunction "(TOSC1)PG4_29") (pintype "bidirectional"))
    )
    (net (code "87") (name "unconnected-(IC3-(TOSC2)PG3-Pad28)") (class "Default")
      (node (ref "IC3") (pin "28") (pinfunction "(TOSC2)PG3_28") (pintype "bidirectional"))
    )
    (net (code "88") (name "unconnected-(IC3-(WR)PG0-Pad51)") (class "Default")
      (node (ref "IC3") (pin "51") (pinfunction "(WR)PG0_51") (pintype "bidirectional"))
    )
    (net (code "89") (name "unconnected-(IC3-(XCK0{slash}AIN0)PE2-Pad4)") (class "Default")
      (node (ref "IC3") (pin "4") (pinfunction "(XCK0/AIN0)PE2_4") (pintype "bidirectional"))
    )
    (net (code "90") (name "unconnected-(IC3-(XCK1)PD5-Pad48)") (class "Default")
      (node (ref "IC3") (pin "48") (pinfunction "(XCK1)PD5_48") (pintype "bidirectional"))
    )
    (net (code "91") (name "unconnected-(IC3-PH2(XCK2)-Pad14)") (class "Default")
      (node (ref "IC3") (pin "14") (pinfunction "PH2(XCK2)_14") (pintype "bidirectional"))
    )
    (net (code "92") (name "unconnected-(IC3-PH3(OC4A)-Pad15)") (class "Default")
      (node (ref "IC3") (pin "15") (pinfunction "PH3(OC4A)_15") (pintype "bidirectional"))
    )
    (net (code "93") (name "unconnected-(IC3-PH4(OC4B)-Pad16)") (class "Default")
      (node (ref "IC3") (pin "16") (pinfunction "PH4(OC4B)_16") (pintype "bidirectional"))
    )
    (net (code "94") (name "unconnected-(IC3-PH5(OC4C)-Pad17)") (class "Default")
      (node (ref "IC3") (pin "17") (pinfunction "PH5(OC4C)_17") (pintype "bidirectional"))
    )
    (net (code "95") (name "unconnected-(IC3-PH6(OC2B)-Pad18)") (class "Default")
      (node (ref "IC3") (pin "18") (pinfunction "PH6(OC2B)_18") (pintype "bidirectional"))
    )
    (net (code "96") (name "unconnected-(IC3-PH7(T4)-Pad27)") (class "Default")
      (node (ref "IC3") (pin "27") (pinfunction "PH7(T4)_27") (pintype "bidirectional"))
    )
    (net (code "97") (name "unconnected-(IC3-PJ2(XCK3{slash}PCINT11)-Pad65)") (class "Default")
      (node (ref "IC3") (pin "65") (pinfunction "PJ2(XCK3/PCINT11)_65") (pintype "bidirectional"))
    )
    (net (code "98") (name "unconnected-(IC3-PJ3(PCINT12)-Pad66)") (class "Default")
      (node (ref "IC3") (pin "66") (pinfunction "PJ3(PCINT12)_66") (pintype "bidirectional"))
    )
    (net (code "99") (name "unconnected-(IC3-PJ4(PCINT13)-Pad67)") (class "Default")
      (node (ref "IC3") (pin "67") (pinfunction "PJ4(PCINT13)_67") (pintype "bidirectional"))
    )
    (net (code "100") (name "unconnected-(IC3-PJ5(PCINT14)-Pad68)") (class "Default")
      (node (ref "IC3") (pin "68") (pinfunction "PJ5(PCINT14)_68") (pintype "bidirectional"))
    )
    (net (code "101") (name "unconnected-(IC3-PJ6(PCINT15)-Pad69)") (class "Default")
      (node (ref "IC3") (pin "69") (pinfunction "PJ6(PCINT15)_69") (pintype "bidirectional"))
    )
    (net (code "102") (name "unconnected-(IC3-PJ7-Pad79)") (class "Default")
      (node (ref "IC3") (pin "79") (pinfunction "PJ7_79") (pintype "bidirectional"))
    )
    (net (code "103") (name "unconnected-(IC3-PK0(ADC8{slash}PCINT16)-Pad89)") (class "Default")
      (node (ref "IC3") (pin "89") (pinfunction "PK0(ADC8/PCINT16)_89") (pintype "bidirectional"))
    )
    (net (code "104") (name "unconnected-(IC3-PK1(ADC9{slash}PCINT17)-Pad88)") (class "Default")
      (node (ref "IC3") (pin "88") (pinfunction "PK1(ADC9/PCINT17)_88") (pintype "bidirectional"))
    )
    (net (code "105") (name "unconnected-(IC3-PK2(ADC10{slash}PCINT18)-Pad87)") (class "Default")
      (node (ref "IC3") (pin "87") (pinfunction "PK2(ADC10/PCINT18)_87") (pintype "bidirectional"))
    )
    (net (code "106") (name "unconnected-(IC3-PK3(ADC11{slash}PCINT19)-Pad86)") (class "Default")
      (node (ref "IC3") (pin "86") (pinfunction "PK3(ADC11/PCINT19)_86") (pintype "bidirectional"))
    )
    (net (code "107") (name "unconnected-(IC3-PK4(ADC12{slash}PCINT20)-Pad85)") (class "Default")
      (node (ref "IC3") (pin "85") (pinfunction "PK4(ADC12/PCINT20)_85") (pintype "bidirectional"))
    )
    (net (code "108") (name "unconnected-(IC3-PK5(ADC13{slash}PCINT21)-Pad84)") (class "Default")
      (node (ref "IC3") (pin "84") (pinfunction "PK5(ADC13/PCINT21)_84") (pintype "bidirectional"))
    )
    (net (code "109") (name "unconnected-(IC3-PK6(ADC14{slash}PCINT22)-Pad83)") (class "Default")
      (node (ref "IC3") (pin "83") (pinfunction "PK6(ADC14/PCINT22)_83") (pintype "bidirectional"))
    )
    (net (code "110") (name "unconnected-(IC3-PK7(ADC15{slash}PCINT23)-Pad82)") (class "Default")
      (node (ref "IC3") (pin "82") (pinfunction "PK7(ADC15/PCINT23)_82") (pintype "bidirectional"))
    )
    (net (code "111") (name "unconnected-(IC3-PL0(ICP4)-Pad35)") (class "Default")
      (node (ref "IC3") (pin "35") (pinfunction "PL0(ICP4)_35") (pintype "bidirectional"))
    )
    (net (code "112") (name "unconnected-(IC3-PL1(ICP5)-Pad36)") (class "Default")
      (node (ref "IC3") (pin "36") (pinfunction "PL1(ICP5)_36") (pintype "bidirectional"))
    )
    (net (code "113") (name "unconnected-(IC3-PL2(T5)-Pad37)") (class "Default")
      (node (ref "IC3") (pin "37") (pinfunction "PL2(T5)_37") (pintype "bidirectional"))
    )
    (net (code "114") (name "unconnected-(IC3-PL3(OC5A)-Pad38)") (class "Default")
      (node (ref "IC3") (pin "38") (pinfunction "PL3(OC5A)_38") (pintype "bidirectional"))
    )
    (net (code "115") (name "unconnected-(IC3-PL4(OC5B)-Pad39)") (class "Default")
      (node (ref "IC3") (pin "39") (pinfunction "PL4(OC5B)_39") (pintype "bidirectional"))
    )
    (net (code "116") (name "unconnected-(IC3-PL5(OC5C)-Pad40)") (class "Default")
      (node (ref "IC3") (pin "40") (pinfunction "PL5(OC5C)_40") (pintype "bidirectional"))
    )
    (net (code "117") (name "unconnected-(IC3-PL6-Pad41)") (class "Default")
      (node (ref "IC3") (pin "41") (pinfunction "PL6_41") (pintype "bidirectional"))
    )
    (net (code "118") (name "unconnected-(IC3-PL7-Pad42)") (class "Default")
      (node (ref "IC3") (pin "42") (pinfunction "PL7_42") (pintype "bidirectional"))
    )
    (net (code "119") (name "unconnected-(J3-Pad4)") (class "Default")
      (node (ref "J3") (pin "4") (pinfunction "4_4") (pintype "passive"))
    )
    (net (code "120") (name "unconnected-(J3-Pad5)") (class "Default")
      (node (ref "J3") (pin "5") (pinfunction "5_5") (pintype "passive"))
    )
    (net (code "121") (name "unconnected-(J3-Pad6)") (class "Default")
      (node (ref "J3") (pin "6") (pinfunction "6_6") (pintype "passive"))
    )
    (net (code "122") (name "unconnected-(J3-Pad7)") (class "Default")
      (node (ref "J3") (pin "7") (pinfunction "7_7") (pintype "passive"))
    )
    (net (code "123") (name "unconnected-(J3-Pad8)") (class "Default")
      (node (ref "J3") (pin "8") (pinfunction "8_8") (pintype "passive"))
    )
    (net (code "124") (name "unconnected-(J3-Pad9)") (class "Default")
      (node (ref "J3") (pin "9") (pinfunction "9_9") (pintype "passive"))
    )
    (net (code "125") (name "unconnected-(J3-Pad10)") (class "Default")
      (node (ref "J3") (pin "10") (pinfunction "10_10") (pintype "passive"))
    )
    (net (code "126") (name "unconnected-(J3-Pad11)") (class "Default")
      (node (ref "J3") (pin "11") (pinfunction "11_11") (pintype "passive"))
    )
    (net (code "127") (name "unconnected-(J3-Pad12)") (class "Default")
      (node (ref "J3") (pin "12") (pinfunction "12_12") (pintype "passive"))
    )
    (net (code "128") (name "unconnected-(J3-Pad21)") (class "Default")
      (node (ref "J3") (pin "21") (pinfunction "21_21") (pintype "passive"))
    )
    (net (code "129") (name "unconnected-(J3-Pad22)") (class "Default")
      (node (ref "J3") (pin "22") (pinfunction "22_22") (pintype "passive"))
    )
    (net (code "130") (name "unconnected-(J3-Pad23)") (class "Default")
      (node (ref "J3") (pin "23") (pinfunction "23_23") (pintype "passive"))
    )
    (net (code "131") (name "unconnected-(J3-Pad24)") (class "Default")
      (node (ref "J3") (pin "24") (pinfunction "24_24") (pintype "passive"))
    )
    (net (code "132") (name "unconnected-(J3-Pad27)") (class "Default")
      (node (ref "J3") (pin "27") (pinfunction "27_27") (pintype "passive"))
    )
    (net (code "133") (name "unconnected-(J3-Pad28)") (class "Default")
      (node (ref "J3") (pin "28") (pinfunction "28_28") (pintype "passive"))
    )
    (net (code "134") (name "unconnected-(J3-Pad29)") (class "Default")
      (node (ref "J3") (pin "29") (pinfunction "29_29") (pintype "passive"))
    )
    (net (code "135") (name "unconnected-(J3-Pad30)") (class "Default")
      (node (ref "J3") (pin "30") (pinfunction "30_30") (pintype "passive"))
    )
    (net (code "136") (name "unconnected-(J3-Pad31)") (class "Default")
      (node (ref "J3") (pin "31") (pinfunction "31_31") (pintype "passive"))
    )
    (net (code "137") (name "unconnected-(J3-Pad32)") (class "Default")
      (node (ref "J3") (pin "32") (pinfunction "32_32") (pintype "passive"))
    )
    (net (code "138") (name "unconnected-(J3-Pad33)") (class "Default")
      (node (ref "J3") (pin "33") (pinfunction "33_33") (pintype "passive"))
    )
    (net (code "139") (name "unconnected-(J3-Pad34)") (class "Default")
      (node (ref "J3") (pin "34") (pinfunction "34_34") (pintype "passive"))
    )
    (net (code "140") (name "unconnected-(J3-Pad35)") (class "Default")
      (node (ref "J3") (pin "35") (pinfunction "35_35") (pintype "passive"))
    )
    (net (code "141") (name "unconnected-(J3-Pad36)") (class "Default")
      (node (ref "J3") (pin "36") (pinfunction "36_36") (pintype "passive"))
    )
    (net (code "142") (name "unconnected-(J3-Pad37)") (class "Default")
      (node (ref "J3") (pin "37") (pinfunction "37_37") (pintype "passive"))
    )
    (net (code "143") (name "unconnected-(J3-Pad38)") (class "Default")
      (node (ref "J3") (pin "38") (pinfunction "38_38") (pintype "passive"))
    )
    (net (code "144") (name "unconnected-(J3-Pad39)") (class "Default")
      (node (ref "J3") (pin "39") (pinfunction "39_39") (pintype "passive"))
    )
    (net (code "145") (name "unconnected-(J3-Pad40)") (class "Default")
      (node (ref "J3") (pin "40") (pinfunction "40_40") (pintype "passive"))
    )
    (net (code "146") (name "unconnected-(J3-Pad41)") (class "Default")
      (node (ref "J3") (pin "41") (pinfunction "41_41") (pintype "passive"))
    )
    (net (code "147") (name "unconnected-(J3-Pad42)") (class "Default")
      (node (ref "J3") (pin "42") (pinfunction "42_42") (pintype "passive"))
    )
    (net (code "148") (name "unconnected-(J3-Pad43)") (class "Default")
      (node (ref "J3") (pin "43") (pinfunction "43_43") (pintype "passive"))
    )
    (net (code "149") (name "unconnected-(J3-Pad44)") (class "Default")
      (node (ref "J3") (pin "44") (pinfunction "44_44") (pintype "passive"))
    )
    (net (code "150") (name "unconnected-(J3-Pad45)") (class "Default")
      (node (ref "J3") (pin "45") (pinfunction "45_45") (pintype "passive"))
    )
    (net (code "151") (name "unconnected-(J3-Pad46)") (class "Default")
      (node (ref "J3") (pin "46") (pinfunction "46_46") (pintype "passive"))
    )
    (net (code "152") (name "unconnected-(J3-Pad47)") (class "Default")
      (node (ref "J3") (pin "47") (pinfunction "47_47") (pintype "passive"))
    )
    (net (code "153") (name "unconnected-(J3-Pad48)") (class "Default")
      (node (ref "J3") (pin "48") (pinfunction "48_48") (pintype "passive"))
    )
    (net (code "154") (name "unconnected-(RADIO-Pad2)") (class "Default")
      (node (ref "RADIO") (pin "2") (pinfunction "2_2") (pintype "passive"))
    )
    (net (code "155") (name "unconnected-(RADIO-Pad4)") (class "Default")
      (node (ref "RADIO") (pin "4") (pinfunction "4_4") (pintype "passive"))
    )
    (net (code "156") (name "unconnected-(RADIO-Pad7)") (class "Default")
      (node (ref "RADIO") (pin "7") (pinfunction "7_7") (pintype "passive"))
    )
    (net (code "157") (name "unconnected-(RADIO-Pad8)") (class "Default")
      (node (ref "RADIO") (pin "8") (pinfunction "8_8") (pintype "passive"))
    )
    (net (code "158") (name "unconnected-(RADIO-Pad9)") (class "Default")
      (node (ref "RADIO") (pin "9") (pinfunction "9_9") (pintype "passive"))
    )
    (net (code "159") (name "unconnected-(SERIAL-Pad1)") (class "Default")
      (node (ref "SERIAL") (pin "1") (pinfunction "1_1") (pintype "passive"))
    )
    (net (code "160") (name "unconnected-(SERIAL-Pad6)") (class "Default")
      (node (ref "SERIAL") (pin "6") (pinfunction "6_6") (pintype "passive"))
    )
    (net (code "161") (name "unconnected-(SERIAL-Pad7)") (class "Default")
      (node (ref "SERIAL") (pin "7") (pinfunction "7_7") (pintype "passive"))
    )
    (net (code "162") (name "unconnected-(SERIAL-Pad8)") (class "Default")
      (node (ref "SERIAL") (pin "8") (pinfunction "8_8") (pintype "passive"))
    )
    (net (code "163") (name "unconnected-(SERIAL-Pad9)") (class "Default")
      (node (ref "SERIAL") (pin "9") (pinfunction "9_9") (pintype "passive"))
    )
    (net (code "164") (name "unconnected-(TEMP-NC-Pad3)") (class "Default")
      (node (ref "TEMP") (pin "3") (pinfunction "NC_3") (pintype "bidirectional"))
    )
    (net (code "165") (name "unconnected-(TEMP-NC1-Pad2)") (class "Default")
      (node (ref "TEMP") (pin "2") (pinfunction "NC1_2") (pintype "bidirectional"))
    )
    (net (code "166") (name "unconnected-(TEMP-NC2-Pad5)") (class "Default")
      (node (ref "TEMP") (pin "5") (pinfunction "NC2_5") (pintype "bidirectional"))
    )
    (net (code "167") (name "unconnected-(TEMP-NC3-Pad6)") (class "Default")
      (node (ref "TEMP") (pin "6") (pinfunction "NC3_6") (pintype "bidirectional"))
    )
    (net (code "168") (name "unconnected-(TEMP-NC4-Pad7)") (class "Default")
      (node (ref "TEMP") (pin "7") (pinfunction "NC4_7") (pintype "bidirectional"))
    )
    (net (code "169") (name "unconnected-(U1-SQ-Pad1)") (class "Default")
      (node (ref "U1") (pin "1") (pinfunction "SQ_1") (pintype "output"))
    )
    (net (code "170") (name "unconnected-(U3-4Y-Pad10)") (class "Default")
      (node (ref "U3") (pin "10") (pinfunction "4Y_10") (pintype "bidirectional"))
    )
    (net (code "171") (name "unconnected-(U3-5Y-Pad12)") (class "Default")
      (node (ref "U3") (pin "12") (pinfunction "5Y_12") (pintype "bidirectional"))
    )
    (net (code "172") (name "unconnected-(U3-6Y-Pad15)") (class "Default")
      (node (ref "U3") (pin "15") (pinfunction "6Y_15") (pintype "bidirectional"))
    )
    (net (code "173") (name "unconnected-(U4-GATEP-Pad3)") (class "Default")
      (node (ref "U4") (pin "3") (pinfunction "GATEP_3") (pintype "passive"))
    )
    (net (code "174") (name "unconnected-(U4-~{PWRGD}-Pad8)") (class "Default")
      (node (ref "U4") (pin "8") (pinfunction "~{PWRGD}_8") (pintype "output"))
    )
    (net (code "175") (name "unconnected-(U5-GATEP-Pad3)") (class "Default")
      (node (ref "U5") (pin "3") (pinfunction "GATEP_3") (pintype "passive"))
    )
    (net (code "176") (name "unconnected-(U5-~{PWRGD}-Pad8)") (class "Default")
      (node (ref "U5") (pin "8") (pinfunction "~{PWRGD}_8") (pintype "output"))
    )
    (net (code "177") (name "unconnected-(U6-GATEP-Pad3)") (class "Default")
      (node (ref "U6") (pin "3") (pinfunction "GATEP_3") (pintype "passive"))
    )
    (net (code "178") (name "unconnected-(U6-~{PWRGD}-Pad8)") (class "Default")
      (node (ref "U6") (pin "8") (pinfunction "~{PWRGD}_8") (pintype "output"))
    )
  )
)
